# lower_traced_flip2040.net
KiCad netlist of a schematic drawn in EAGLE
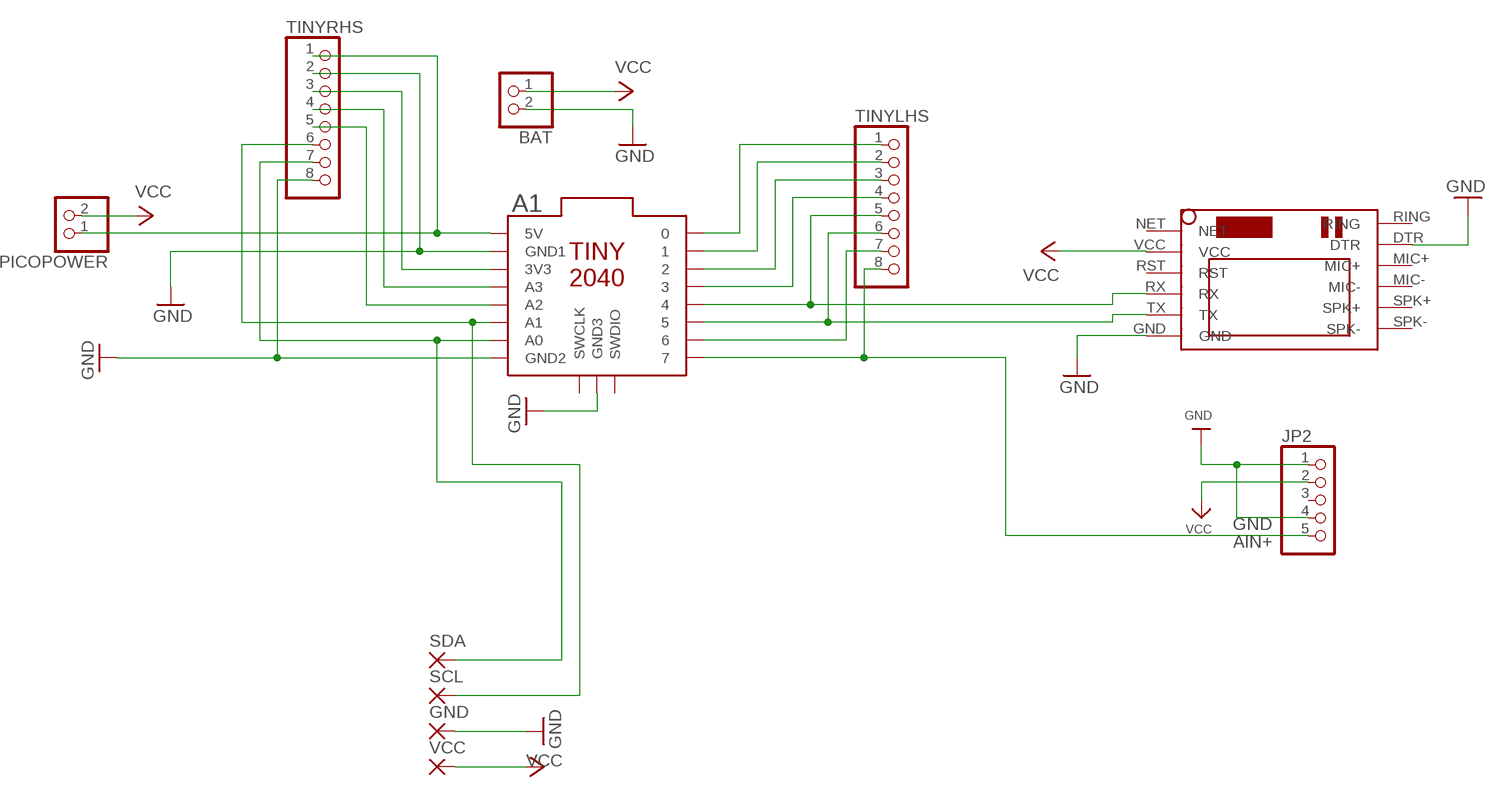
[diagram p0: schematic, sheet 1]

(export (version "E")
  (design (tool "Eeschema 10.0.6"))
  (components
    (comp (ref "A1")
      (value "TINY2040")
      (footprint "eagle-import:TINY2040")
      (libsource (lib "eagle-import") (part "TINY2040"))
    )
    (comp (ref "BAT")
      (value "JST_2PIN-THM-RA")
      (footprint "eagle-import:JST-PH-2-THM-RA")
      (libsource (lib "eagle-import") (part "JST_2PIN-THM-RA"))
    )
    (comp (ref "GND")
      (value "3,17/1,1")
      (footprint "eagle-import:3,17_1,1")
      (libsource (lib "eagle-import") (part "3,17/1,1"))
    )
    (comp (ref "JP2")
      (value "HEADER-1X570MIL")
      (footprint "eagle-import:1X05_ROUND_70")
      (libsource (lib "eagle-import") (part "HEADER-1X570MIL"))
    )
    (comp (ref "PICOPOWER")
      (value "PINHD-1X2")
      (footprint "eagle-import:1X02")
      (libsource (lib "eagle-import") (part "PINHD-1X2"))
    )
    (comp (ref "SCL")
      (value "3,17/1,1")
      (footprint "eagle-import:3,17_1,1")
      (libsource (lib "eagle-import") (part "3,17/1,1"))
    )
    (comp (ref "SDA")
      (value "3,17/1,1")
      (footprint "eagle-import:3,17_1,1")
      (libsource (lib "eagle-import") (part "3,17/1,1"))
    )
    (comp (ref "TINYLHS")
      (value "PINHD-1X8")
      (footprint "eagle-import:1X08")
      (libsource (lib "eagle-import") (part "PINHD-1X8"))
    )
    (comp (ref "TINYRHS")
      (value "PINHD-1X8")
      (footprint "eagle-import:1X08")
      (libsource (lib "eagle-import") (part "PINHD-1X8"))
    )
    (comp (ref "U$2")
      (value "SIM800LMODULE")
      (footprint "eagle-import:SIM800LMODULE")
      (libsource (lib "eagle-import") (part "SIM800LMODULE"))
    )
    (comp (ref "VCC")
      (value "3,17/1,1")
      (footprint "eagle-import:3,17_1,1")
      (libsource (lib "eagle-import") (part "3,17/1,1"))
    )
  )
  (nets
    (net (code "1") (name "/AIN+") (class "Default")
      (node (ref "A1") (pin "7") (pinfunction "7_7") (pintype "bidirectional"))
      (node (ref "JP2") (pin "5") (pinfunction "5_5") (pintype "passive"))
      (node (ref "TINYLHS") (pin "8") (pinfunction "8_8") (pintype "passive"))
    )
    (net (code "2") (name "GND") (class "Default")
      (node (ref "A1") (pin "GND1") (pinfunction "GND1_GND1") (pintype "bidirectional"))
      (node (ref "A1") (pin "GND2") (pinfunction "GND2_GND2") (pintype "bidirectional"))
      (node (ref "A1") (pin "GND3") (pinfunction "GND3_GND3") (pintype "bidirectional"))
      (node (ref "BAT") (pin "2") (pinfunction "1_2") (pintype "passive"))
      (node (ref "GND") (pin "1") (pinfunction "P_1") (pintype "passive"))
      (node (ref "JP2") (pin "1") (pinfunction "1_1") (pintype "passive"))
      (node (ref "JP2") (pin "4") (pinfunction "4_4") (pintype "passive"))
      (node (ref "TINYRHS") (pin "2") (pinfunction "2_2") (pintype "passive"))
      (node (ref "TINYRHS") (pin "8") (pinfunction "8_8") (pintype "passive"))
      (node (ref "U$2") (pin "DTR") (pinfunction "DTR_DTR") (pintype "bidirectional"))
      (node (ref "U$2") (pin "GND") (pinfunction "GND_GND") (pintype "bidirectional"))
    )
    (net (code "3") (name "Net-(A1-Pad0)") (class "Default")
      (node (ref "A1") (pin "0") (pinfunction "0_0") (pintype "bidirectional"))
      (node (ref "TINYLHS") (pin "1") (pinfunction "1_1") (pintype "passive"))
    )
    (net (code "4") (name "Net-(A1-Pad1)") (class "Default")
      (node (ref "A1") (pin "1") (pinfunction "1_1") (pintype "bidirectional"))
      (node (ref "TINYLHS") (pin "2") (pinfunction "2_2") (pintype "passive"))
    )
    (net (code "5") (name "Net-(A1-Pad2)") (class "Default")
      (node (ref "A1") (pin "2") (pinfunction "2_2") (pintype "bidirectional"))
      (node (ref "TINYLHS") (pin "3") (pinfunction "3_3") (pintype "passive"))
    )
    (net (code "6") (name "Net-(A1-Pad3)") (class "Default")
      (node (ref "A1") (pin "3") (pinfunction "3_3") (pintype "bidirectional"))
      (node (ref "TINYLHS") (pin "4") (pinfunction "4_4") (pintype "passive"))
    )
    (net (code "7") (name "Net-(A1-Pad3V3)") (class "Default")
      (node (ref "A1") (pin "3V3") (pinfunction "3V3_3V3") (pintype "bidirectional"))
      (node (ref "TINYRHS") (pin "3") (pinfunction "3_3") (pintype "passive"))
    )
    (net (code "8") (name "Net-(A1-Pad4)") (class "Default")
      (node (ref "A1") (pin "4") (pinfunction "4_4") (pintype "bidirectional"))
      (node (ref "TINYLHS") (pin "5") (pinfunction "5_5") (pintype "passive"))
      (node (ref "U$2") (pin "RX") (pinfunction "RX_RX") (pintype "bidirectional"))
    )
    (net (code "9") (name "Net-(A1-Pad5)") (class "Default")
      (node (ref "A1") (pin "5") (pinfunction "5_5") (pintype "bidirectional"))
      (node (ref "TINYLHS") (pin "6") (pinfunction "6_6") (pintype "passive"))
      (node (ref "U$2") (pin "TX") (pinfunction "TX_TX") (pintype "bidirectional"))
    )
    (net (code "10") (name "Net-(A1-Pad5V)") (class "Default")
      (node (ref "A1") (pin "5V") (pinfunction "5V_5V") (pintype "bidirectional"))
      (node (ref "PICOPOWER") (pin "1") (pinfunction "1_1") (pintype "passive"))
      (node (ref "TINYRHS") (pin "1") (pinfunction "1_1") (pintype "passive"))
    )
    (net (code "11") (name "Net-(A1-Pad6)") (class "Default")
      (node (ref "A1") (pin "6") (pinfunction "6_6") (pintype "bidirectional"))
      (node (ref "TINYLHS") (pin "7") (pinfunction "7_7") (pintype "passive"))
    )
    (net (code "12") (name "Net-(A1-PadA2)") (class "Default")
      (node (ref "A1") (pin "A2") (pinfunction "A2_A2") (pintype "bidirectional"))
      (node (ref "TINYRHS") (pin "5") (pinfunction "5_5") (pintype "passive"))
    )
    (net (code "13") (name "Net-(A1-PadA3)") (class "Default")
      (node (ref "A1") (pin "A3") (pinfunction "A3_A3") (pintype "bidirectional"))
      (node (ref "TINYRHS") (pin "4") (pinfunction "4_4") (pintype "passive"))
    )
    (net (code "14") (name "Net-(SCL-P)") (class "Default")
      (node (ref "A1") (pin "A1") (pinfunction "A1_A1") (pintype "bidirectional"))
      (node (ref "SCL") (pin "1") (pinfunction "P_1") (pintype "passive"))
      (node (ref "TINYRHS") (pin "6") (pinfunction "6_6") (pintype "passive"))
    )
    (net (code "15") (name "Net-(SDA-P)") (class "Default")
      (node (ref "A1") (pin "A0") (pinfunction "A0_A0") (pintype "bidirectional"))
      (node (ref "SDA") (pin "1") (pinfunction "P_1") (pintype "passive"))
      (node (ref "TINYRHS") (pin "7") (pinfunction "7_7") (pintype "passive"))
    )
    (net (code "16") (name "VCC") (class "Default")
      (node (ref "BAT") (pin "1") (pinfunction "2_1") (pintype "passive"))
      (node (ref "JP2") (pin "2") (pinfunction "2_2") (pintype "passive"))
      (node (ref "PICOPOWER") (pin "2") (pinfunction "2_2") (pintype "passive"))
      (node (ref "U$2") (pin "VCC") (pinfunction "VCC_VCC") (pintype "bidirectional"))
      (node (ref "VCC") (pin "1") (pinfunction "P_1") (pintype "passive"))
    )
    (net (code "17") (name "unconnected-(A1-PadSWCLK)") (class "Default")
      (node (ref "A1") (pin "SWCLK") (pinfunction "SWCLK_SWCLK") (pintype "bidirectional"))
    )
    (net (code "18") (name "unconnected-(A1-PadSWDIO)") (class "Default")
      (node (ref "A1") (pin "SWDIO") (pinfunction "SWDIO_SWDIO") (pintype "bidirectional"))
    )
    (net (code "19") (name "unconnected-(JP2-Pad3)") (class "Default")
      (node (ref "JP2") (pin "3") (pinfunction "3_3") (pintype "passive"))
    )
    (net (code "20") (name "unconnected-(U$2-PadMIC+)") (class "Default")
      (node (ref "U$2") (pin "MIC+") (pinfunction "MIC+_MIC+") (pintype "bidirectional"))
    )
    (net (code "21") (name "unconnected-(U$2-PadMIC-)") (class "Default")
      (node (ref "U$2") (pin "MIC-") (pinfunction "MIC-_MIC-") (pintype "bidirectional"))
    )
    (net (code "22") (name "unconnected-(U$2-PadNET)") (class "Default")
      (node (ref "U$2") (pin "NET") (pinfunction "NET_NET") (pintype "bidirectional"))
    )
    (net (code "23") (name "unconnected-(U$2-PadRING)") (class "Default")
      (node (ref "U$2") (pin "RING") (pinfunction "RING_RING") (pintype "bidirectional"))
    )
    (net (code "24") (name "unconnected-(U$2-PadRST)") (class "Default")
      (node (ref "U$2") (pin "RST") (pinfunction "RST_RST") (pintype "bidirectional"))
    )
    (net (code "25") (name "unconnected-(U$2-PadSPK+)") (class "Default")
      (node (ref "U$2") (pin "SPK+") (pinfunction "SPK+_SPK+") (pintype "bidirectional"))
    )
    (net (code "26") (name "unconnected-(U$2-PadSPK-)") (class "Default")
      (node (ref "U$2") (pin "SPK-") (pinfunction "SPK-_SPK-") (pintype "bidirectional"))
    )
  )
)
